# untitled.net
KiCad netlist of a schematic drawn in EAGLE
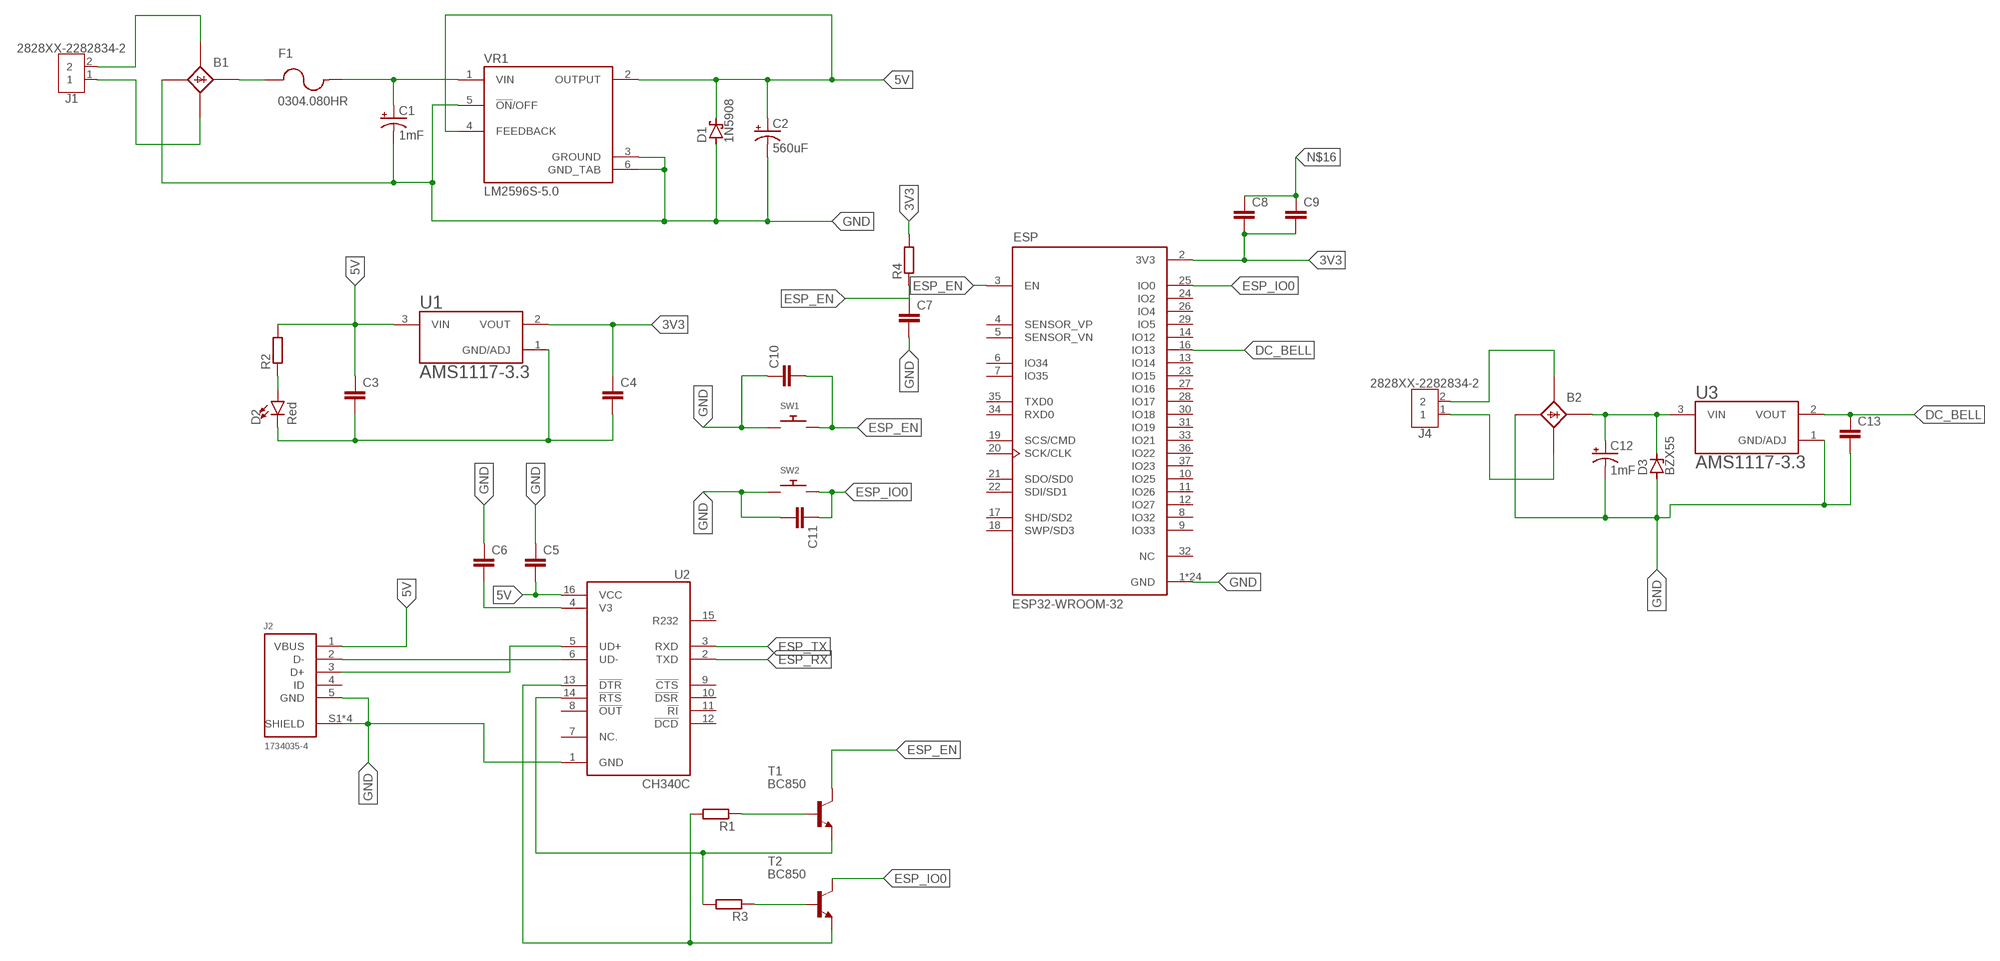
[diagram p0: schematic, sheet 1]

(export (version "E")
  (design (tool "Eeschema 10.0.6"))
  (components
    (comp (ref "B1")
      (value "B25A-")
      (footprint "eagle-import:B25A-")
      (libsource (lib "eagle-import") (part "B25A-"))
    )
    (comp (ref "B2")
      (value "B25A-")
      (footprint "eagle-import:B25A-")
      (libsource (lib "eagle-import") (part "B25A-"))
    )
    (comp (ref "C1")
      (value "1mF")
      (footprint "eagle-import:CPOL-RADIAL-5MM-10MM")
      (libsource (lib "eagle-import") (part "1000UF-RADIAL-5MM-25V-20%"))
    )
    (comp (ref "C2")
      (value "560uF")
      (footprint "eagle-import:PANASONIC_G")
      (libsource (lib "eagle-import") (part "560UF-PANASONIC_G-25V-20%"))
    )
    (comp (ref "C3")
      (value "C-EUC1206K")
      (footprint "eagle-import:C1206K")
      (libsource (lib "eagle-import") (part "C-EUC1206K"))
    )
    (comp (ref "C4")
      (value "C-EUC1206K")
      (footprint "eagle-import:C1206K")
      (libsource (lib "eagle-import") (part "C-EUC1206K"))
    )
    (comp (ref "C5")
      (value "C-EUC1206K")
      (footprint "eagle-import:C1206K")
      (libsource (lib "eagle-import") (part "C-EUC1206K"))
    )
    (comp (ref "C6")
      (value "C-EUC1206K")
      (footprint "eagle-import:C1206K")
      (libsource (lib "eagle-import") (part "C-EUC1206K"))
    )
    (comp (ref "C7")
      (value "C-EUC1206K")
      (footprint "eagle-import:C1206K")
      (libsource (lib "eagle-import") (part "C-EUC1206K"))
    )
    (comp (ref "C8")
      (value "C-EUC1206K")
      (footprint "eagle-import:C1206K")
      (libsource (lib "eagle-import") (part "C-EUC1206K"))
    )
    (comp (ref "C9")
      (value "C-EUC1206K")
      (footprint "eagle-import:C1206K")
      (libsource (lib "eagle-import") (part "C-EUC1206K"))
    )
    (comp (ref "C10")
      (value "C-EUC1206K")
      (footprint "eagle-import:C1206K")
      (libsource (lib "eagle-import") (part "C-EUC1206K"))
    )
    (comp (ref "C11")
      (value "C-EUC1206K")
      (footprint "eagle-import:C1206K")
      (libsource (lib "eagle-import") (part "C-EUC1206K"))
    )
    (comp (ref "C12")
      (value "1mF")
      (footprint "eagle-import:CPOL-RADIAL-5MM-10MM")
      (libsource (lib "eagle-import") (part "1000UF-RADIAL-5MM-25V-20%"))
    )
    (comp (ref "C13")
      (value "C-EUC1206K")
      (footprint "eagle-import:C1206K")
      (libsource (lib "eagle-import") (part "C-EUC1206K"))
    )
    (comp (ref "D1")
      (value "1N5908")
      (footprint "eagle-import:C4111-15")
      (libsource (lib "eagle-import") (part "1N5908"))
    )
    (comp (ref "D2")
      (value "Red")
      (footprint "eagle-import:LED-0603")
      (libsource (lib "eagle-import") (part "LED-RED-0603-WE"))
    )
    (comp (ref "D3")
      (value "BZX55")
      (footprint "eagle-import:DO35Z10")
      (libsource (lib "eagle-import") (part "BZX55"))
    )
    (comp (ref "ESP")
      (value "ESP32-WROOM-32")
      (footprint "eagle-import:MODULE_ESP32-WROOM-32")
      (fields (field (name "MF") "Espressif Systems"))
      (libsource (lib "eagle-import") (part "ESP32-WROOM-32"))
    )
    (comp (ref "F1")
      (value "0304.080HR")
      (footprint "eagle-import:0304.080HR")
      (fields (field (name "MANUFACTURER") "Littelfuse Inc.") (field (name "CREATED_BY") "PCBLayout.com"))
      (libsource (lib "eagle-import") (part "0304.080HR"))
    )
    (comp (ref "J1")
      (value "2828XX-2282834-2")
      (footprint "eagle-import:TERMBLK_254-2N")
      (fields (field (name "MANUFACTURER") "TE Connectivity AMP Connectors") (field (name "MPN") "282834-2 "))
      (libsource (lib "eagle-import") (part "2828XX-2282834-2"))
    )
    (comp (ref "J2")
      (value "1734035-4")
      (footprint "eagle-import:1734035-4")
      (fields
        (field (name "DIGIKEY_PARTNO") "A121554TR-ND")
        (field (name "MANUFACTURER") "TE Connectivity AMP Connectors")
        (field (name "CREATED_BY") "PCBLayout.com")
      )
      (libsource (lib "eagle-import") (part "1734035-4"))
    )
    (comp (ref "J4")
      (value "2828XX-2282834-2")
      (footprint "eagle-import:TERMBLK_254-2N")
      (fields (field (name "MANUFACTURER") "TE Connectivity AMP Connectors") (field (name "MPN") "282834-2 "))
      (libsource (lib "eagle-import") (part "2828XX-2282834-2"))
    )
    (comp (ref "R1")
      (value "R-EU_R5025W")
      (footprint "eagle-import:R5025W")
      (libsource (lib "eagle-import") (part "R-EU_R5025W"))
    )
    (comp (ref "R2")
      (value "R-EU_R5025W")
      (footprint "eagle-import:R5025W")
      (libsource (lib "eagle-import") (part "R-EU_R5025W"))
    )
    (comp (ref "R3")
      (value "R-EU_R5025W")
      (footprint "eagle-import:R5025W")
      (libsource (lib "eagle-import") (part "R-EU_R5025W"))
    )
    (comp (ref "R4")
      (value "R-EU_R5025W")
      (footprint "eagle-import:R5025W")
      (libsource (lib "eagle-import") (part "R-EU_R5025W"))
    )
    (comp (ref "SW1")
      (value "SWITCH_PUSHBUTTONSOFTTOUCHSMD_SJ")
      (footprint "eagle-import:PUSHBUTTON_SMD_SJ")
      (libsource (lib "eagle-import") (part "SWITCH_PUSHBUTTONSOFTTOUCHSMD_SJ"))
    )
    (comp (ref "SW2")
      (value "SWITCH_PUSHBUTTONSOFTTOUCHSMD_SJ")
      (footprint "eagle-import:PUSHBUTTON_SMD_SJ")
      (libsource (lib "eagle-import") (part "SWITCH_PUSHBUTTONSOFTTOUCHSMD_SJ"))
    )
    (comp (ref "T1")
      (value "BC850")
      (footprint "eagle-import:SOT23")
      (libsource (lib "eagle-import") (part "BC850"))
    )
    (comp (ref "T2")
      (value "BC850")
      (footprint "eagle-import:SOT23")
      (libsource (lib "eagle-import") (part "BC850"))
    )
    (comp (ref "U1")
      (value "AMS1117-3.3")
      (footprint "eagle-import:SOT229P700X180-4N")
      (fields (field (name "MF") "Advanced Monolithic Systems"))
      (libsource (lib "eagle-import") (part "AMS1117-3.3"))
    )
    (comp (ref "U2")
      (value "CH340C")
      (footprint "eagle-import:SOIC127P600X180-16N")
      (fields (field (name "MF") "WCH"))
      (libsource (lib "eagle-import") (part "CH340C"))
    )
    (comp (ref "U3")
      (value "AMS1117-3.3")
      (footprint "eagle-import:SOT229P700X180-4N")
      (fields (field (name "MF") "Advanced Monolithic Systems"))
      (libsource (lib "eagle-import") (part "AMS1117-3.3"))
    )
    (comp (ref "VR1")
      (value "LM2596S-5.0")
      (footprint "eagle-import:TO170P1524X483-6N")
      (fields (field (name "MF") "Texas"))
      (libsource (lib "eagle-import") (part "LM2596S-5.0"))
    )
  )
  (nets
    (net (code "1") (name "3V3") (class "Default")
      (node (ref "C4") (pin "1") (pinfunction "1_1") (pintype "passive"))
      (node (ref "C8") (pin "2") (pinfunction "2_2") (pintype "passive"))
      (node (ref "C9") (pin "2") (pinfunction "2_2") (pintype "passive"))
      (node (ref "ESP") (pin "2") (pinfunction "3V3_2") (pintype "power_in"))
      (node (ref "R4") (pin "2") (pinfunction "2_2") (pintype "passive"))
      (node (ref "U1") (pin "2") (pinfunction "VOUT_2") (pintype "output"))
    )
    (net (code "2") (name "5V") (class "Default")
      (node (ref "C2") (pin "+") (pinfunction "+_+") (pintype "passive"))
      (node (ref "C3") (pin "1") (pinfunction "1_1") (pintype "passive"))
      (node (ref "C5") (pin "2") (pinfunction "2_2") (pintype "passive"))
      (node (ref "D1") (pin "C") (pinfunction "C_C") (pintype "passive"))
      (node (ref "J2") (pin "1") (pinfunction "VBUS_1") (pintype "passive"))
      (node (ref "R2") (pin "2") (pinfunction "2_2") (pintype "passive"))
      (node (ref "U1") (pin "3") (pinfunction "VIN_3") (pintype "input"))
      (node (ref "U2") (pin "16") (pinfunction "VCC_16") (pintype "power_in"))
      (node (ref "VR1") (pin "2") (pinfunction "OUTPUT_2") (pintype "output"))
      (node (ref "VR1") (pin "4") (pinfunction "FEEDBACK_4") (pintype "input"))
    )
    (net (code "3") (name "DC_BELL") (class "Default")
      (node (ref "C13") (pin "1") (pinfunction "1_1") (pintype "passive"))
      (node (ref "ESP") (pin "16") (pinfunction "IO13_16") (pintype "bidirectional"))
      (node (ref "U3") (pin "2") (pinfunction "VOUT_2") (pintype "output"))
    )
    (net (code "4") (name "ESP_EN") (class "Default")
      (node (ref "C10") (pin "2") (pinfunction "2_2") (pintype "passive"))
      (node (ref "C7") (pin "1") (pinfunction "1_1") (pintype "passive"))
      (node (ref "ESP") (pin "3") (pinfunction "EN_3") (pintype "input"))
      (node (ref "R4") (pin "1") (pinfunction "1_1") (pintype "passive"))
      (node (ref "SW1") (pin "P$2") (pinfunction "P$2_P$2") (pintype "passive"))
      (node (ref "T1") (pin "3") (pinfunction "C_3") (pintype "passive"))
    )
    (net (code "5") (name "ESP_IO0") (class "Default")
      (node (ref "C11") (pin "1") (pinfunction "1_1") (pintype "passive"))
      (node (ref "ESP") (pin "25") (pinfunction "IO0_25") (pintype "bidirectional"))
      (node (ref "SW2") (pin "P$2") (pinfunction "P$2_P$2") (pintype "passive"))
      (node (ref "T2") (pin "3") (pinfunction "C_3") (pintype "passive"))
    )
    (net (code "6") (name "ESP_RX") (class "Default")
      (node (ref "U2") (pin "2") (pinfunction "TXD_2") (pintype "output"))
    )
    (net (code "7") (name "ESP_TX") (class "Default")
      (node (ref "U2") (pin "3") (pinfunction "RXD_3") (pintype "input"))
    )
    (net (code "8") (name "GND") (class "Default")
      (node (ref "B1") (pin "-1") (pinfunction "-_-1") (pintype "passive"))
      (node (ref "B2") (pin "-1") (pinfunction "-_-1") (pintype "passive"))
      (node (ref "C1") (pin "-") (pinfunction "-_-") (pintype "passive"))
      (node (ref "C10") (pin "1") (pinfunction "1_1") (pintype "passive"))
      (node (ref "C11") (pin "2") (pinfunction "2_2") (pintype "passive"))
      (node (ref "C12") (pin "-") (pinfunction "-_-") (pintype "passive"))
      (node (ref "C13") (pin "2") (pinfunction "2_2") (pintype "passive"))
      (node (ref "C2") (pin "-") (pinfunction "-_-") (pintype "passive"))
      (node (ref "C5") (pin "1") (pinfunction "1_1") (pintype "passive"))
      (node (ref "C6") (pin "1") (pinfunction "1_1") (pintype "passive"))
      (node (ref "C7") (pin "2") (pinfunction "2_2") (pintype "passive"))
      (node (ref "D1") (pin "A") (pinfunction "A_A") (pintype "passive"))
      (node (ref "D3") (pin "A") (pinfunction "A_A") (pintype "passive"))
      (node (ref "ESP") (pin "1") (pinfunction "GND_1") (pintype "power_in"))
      (node (ref "ESP") (pin "15") (pinfunction "GND_15") (pintype "power_in"))
      (node (ref "ESP") (pin "38") (pinfunction "GND_38") (pintype "power_in"))
      (node (ref "ESP") (pin "39_1") (pinfunction "GND_39_1") (pintype "power_in"))
      (node (ref "ESP") (pin "39_10") (pinfunction "GND_39_10") (pintype "power_in"))
      (node (ref "ESP") (pin "39_11") (pinfunction "GND_39_11") (pintype "power_in"))
      (node (ref "ESP") (pin "39_12") (pinfunction "GND_39_12") (pintype "power_in"))
      (node (ref "ESP") (pin "39_13") (pinfunction "GND_39_13") (pintype "power_in"))
      (node (ref "ESP") (pin "39_14") (pinfunction "GND_39_14") (pintype "power_in"))
      (node (ref "ESP") (pin "39_15") (pinfunction "GND_39_15") (pintype "power_in"))
      (node (ref "ESP") (pin "39_16") (pinfunction "GND_39_16") (pintype "power_in"))
      (node (ref "ESP") (pin "39_17") (pinfunction "GND_39_17") (pintype "power_in"))
      (node (ref "ESP") (pin "39_18") (pinfunction "GND_39_18") (pintype "power_in"))
      (node (ref "ESP") (pin "39_19") (pinfunction "GND_39_19") (pintype "power_in"))
      (node (ref "ESP") (pin "39_2") (pinfunction "GND_39_2") (pintype "power_in"))
      (node (ref "ESP") (pin "39_20") (pinfunction "GND_39_20") (pintype "power_in"))
      (node (ref "ESP") (pin "39_21") (pinfunction "GND_39_21") (pintype "power_in"))
      (node (ref "ESP") (pin "39_3") (pinfunction "GND_39_3") (pintype "power_in"))
      (node (ref "ESP") (pin "39_4") (pinfunction "GND_39_4") (pintype "power_in"))
      (node (ref "ESP") (pin "39_5") (pinfunction "GND_39_5") (pintype "power_in"))
      (node (ref "ESP") (pin "39_6") (pinfunction "GND_39_6") (pintype "power_in"))
      (node (ref "ESP") (pin "39_7") (pinfunction "GND_39_7") (pintype "power_in"))
      (node (ref "ESP") (pin "39_8") (pinfunction "GND_39_8") (pintype "power_in"))
      (node (ref "ESP") (pin "39_9") (pinfunction "GND_39_9") (pintype "power_in"))
      (node (ref "J2") (pin "5") (pinfunction "GND_5") (pintype "passive"))
      (node (ref "J2") (pin "S1") (pinfunction "SHIELD_S1") (pintype "power_in"))
      (node (ref "J2") (pin "S2") (pinfunction "SHIELD_S2") (pintype "power_in"))
      (node (ref "J2") (pin "S3") (pinfunction "SHIELD_S3") (pintype "power_in"))
      (node (ref "J2") (pin "S4") (pinfunction "SHIELD_S4") (pintype "power_in"))
      (node (ref "SW1") (pin "P$1") (pinfunction "P$1_P$1") (pintype "passive"))
      (node (ref "SW2") (pin "P$1") (pinfunction "P$1_P$1") (pintype "passive"))
      (node (ref "U2") (pin "1") (pinfunction "GND_1") (pintype "power_in"))
      (node (ref "U3") (pin "1") (pinfunction "GND/ADJ_1") (pintype "power_in"))
      (node (ref "VR1") (pin "3") (pinfunction "GROUND_3") (pintype "power_in"))
      (node (ref "VR1") (pin "5") (pinfunction "~{ON}/OFF_5") (pintype "input"))
      (node (ref "VR1") (pin "6") (pinfunction "GND_TAB_6") (pintype "power_in"))
    )
    (net (code "9") (name "N$16") (class "Default")
      (node (ref "C8") (pin "1") (pinfunction "1_1") (pintype "passive"))
      (node (ref "C9") (pin "1") (pinfunction "1_1") (pintype "passive"))
    )
    (net (code "10") (name "Net-(B1-+-Pad+1)") (class "Default")
      (node (ref "B1") (pin "+1") (pinfunction "+_+1") (pintype "passive"))
      (node (ref "F1") (pin "1") (pinfunction "1_1") (pintype "passive"))
    )
    (net (code "11") (name "Net-(B1-AC1-PadAC1-)") (class "Default")
      (node (ref "B1") (pin "AC1-") (pinfunction "AC1_AC1-") (pintype "passive"))
      (node (ref "J1") (pin "2") (pinfunction "2_2") (pintype "bidirectional"))
    )
    (net (code "12") (name "Net-(B1-AC2-PadAC2-)") (class "Default")
      (node (ref "B1") (pin "AC2-") (pinfunction "AC2_AC2-") (pintype "passive"))
      (node (ref "J1") (pin "1") (pinfunction "1_1") (pintype "bidirectional"))
    )
    (net (code "13") (name "Net-(B2-AC1-PadAC1-)") (class "Default")
      (node (ref "B2") (pin "AC1-") (pinfunction "AC1_AC1-") (pintype "passive"))
      (node (ref "J4") (pin "2") (pinfunction "2_2") (pintype "bidirectional"))
    )
    (net (code "14") (name "Net-(B2-AC2-PadAC2-)") (class "Default")
      (node (ref "B2") (pin "AC2-") (pinfunction "AC2_AC2-") (pintype "passive"))
      (node (ref "J4") (pin "1") (pinfunction "1_1") (pintype "bidirectional"))
    )
    (net (code "15") (name "Net-(D2-PadA)") (class "Default")
      (node (ref "D2") (pin "A") (pinfunction "A_A") (pintype "passive"))
      (node (ref "R2") (pin "1") (pinfunction "1_1") (pintype "passive"))
    )
    (net (code "16") (name "Net-(J2-D+)") (class "Default")
      (node (ref "J2") (pin "3") (pinfunction "D+_3") (pintype "passive"))
      (node (ref "U2") (pin "5") (pinfunction "UD+_5") (pintype "bidirectional"))
    )
    (net (code "17") (name "Net-(J2-D-)") (class "Default")
      (node (ref "J2") (pin "2") (pinfunction "D-_2") (pintype "passive"))
      (node (ref "U2") (pin "6") (pinfunction "UD-_6") (pintype "bidirectional"))
    )
    (net (code "18") (name "Net-(T1-B)") (class "Default")
      (node (ref "R1") (pin "1") (pinfunction "1_1") (pintype "passive"))
      (node (ref "T1") (pin "1") (pinfunction "B_1") (pintype "passive"))
    )
    (net (code "19") (name "Net-(T1-E)") (class "Default")
      (node (ref "R3") (pin "2") (pinfunction "2_2") (pintype "passive"))
      (node (ref "T1") (pin "2") (pinfunction "E_2") (pintype "passive"))
      (node (ref "U2") (pin "14") (pinfunction "~{RTS}_14") (pintype "output"))
    )
    (net (code "20") (name "Net-(T2-B)") (class "Default")
      (node (ref "R3") (pin "1") (pinfunction "1_1") (pintype "passive"))
      (node (ref "T2") (pin "1") (pinfunction "B_1") (pintype "passive"))
    )
    (net (code "21") (name "Net-(T2-E)") (class "Default")
      (node (ref "R1") (pin "2") (pinfunction "2_2") (pintype "passive"))
      (node (ref "T2") (pin "2") (pinfunction "E_2") (pintype "passive"))
      (node (ref "U2") (pin "13") (pinfunction "~{DTR}_13") (pintype "output"))
    )
    (net (code "22") (name "Net-(U1-GND{slash}ADJ)") (class "Default")
      (node (ref "C3") (pin "2") (pinfunction "2_2") (pintype "passive"))
      (node (ref "C4") (pin "2") (pinfunction "2_2") (pintype "passive"))
      (node (ref "D2") (pin "C") (pinfunction "C_C") (pintype "passive"))
      (node (ref "U1") (pin "1") (pinfunction "GND/ADJ_1") (pintype "power_in"))
    )
    (net (code "23") (name "Net-(U2-V3)") (class "Default")
      (node (ref "C6") (pin "2") (pinfunction "2_2") (pintype "passive"))
      (node (ref "U2") (pin "4") (pinfunction "V3_4") (pintype "power_in"))
    )
    (net (code "24") (name "Net-(U3-VIN)") (class "Default")
      (node (ref "B2") (pin "+1") (pinfunction "+_+1") (pintype "passive"))
      (node (ref "C12") (pin "+") (pinfunction "+_+") (pintype "passive"))
      (node (ref "D3") (pin "C") (pinfunction "C_C") (pintype "passive"))
      (node (ref "U3") (pin "3") (pinfunction "VIN_3") (pintype "input"))
    )
    (net (code "25") (name "Net-(VR1-VIN)") (class "Default")
      (node (ref "C1") (pin "+") (pinfunction "+_+") (pintype "passive"))
      (node (ref "F1") (pin "2") (pinfunction "2_2") (pintype "passive"))
      (node (ref "VR1") (pin "1") (pinfunction "VIN_1") (pintype "input"))
    )
    (net (code "26") (name "unconnected-(B1-Pad+)") (class "Default")
      (node (ref "B1") (pin "+") (pinfunction "+_+") (pintype "passive"))
    )
    (net (code "27") (name "unconnected-(B1-Pad-)") (class "Default")
      (node (ref "B1") (pin "-") (pinfunction "-_-") (pintype "passive"))
    )
    (net (code "28") (name "unconnected-(B1-PadAC1)") (class "Default")
      (node (ref "B1") (pin "AC1") (pinfunction "AC1_AC1") (pintype "passive"))
    )
    (net (code "29") (name "unconnected-(B1-PadAC2)") (class "Default")
      (node (ref "B1") (pin "AC2") (pinfunction "AC2_AC2") (pintype "passive"))
    )
    (net (code "30") (name "unconnected-(B2-Pad+)") (class "Default")
      (node (ref "B2") (pin "+") (pinfunction "+_+") (pintype "passive"))
    )
    (net (code "31") (name "unconnected-(B2-Pad-)") (class "Default")
      (node (ref "B2") (pin "-") (pinfunction "-_-") (pintype "passive"))
    )
    (net (code "32") (name "unconnected-(B2-PadAC1)") (class "Default")
      (node (ref "B2") (pin "AC1") (pinfunction "AC1_AC1") (pintype "passive"))
    )
    (net (code "33") (name "unconnected-(B2-PadAC2)") (class "Default")
      (node (ref "B2") (pin "AC2") (pinfunction "AC2_AC2") (pintype "passive"))
    )
    (net (code "34") (name "unconnected-(ESP-IO2-Pad24)") (class "Default")
      (node (ref "ESP") (pin "24") (pinfunction "IO2_24") (pintype "bidirectional"))
    )
    (net (code "35") (name "unconnected-(ESP-IO4-Pad26)") (class "Default")
      (node (ref "ESP") (pin "26") (pinfunction "IO4_26") (pintype "bidirectional"))
    )
    (net (code "36") (name "unconnected-(ESP-IO5-Pad29)") (class "Default")
      (node (ref "ESP") (pin "29") (pinfunction "IO5_29") (pintype "bidirectional"))
    )
    (net (code "37") (name "unconnected-(ESP-IO12-Pad14)") (class "Default")
      (node (ref "ESP") (pin "14") (pinfunction "IO12_14") (pintype "bidirectional"))
    )
    (net (code "38") (name "unconnected-(ESP-IO14-Pad13)") (class "Default")
      (node (ref "ESP") (pin "13") (pinfunction "IO14_13") (pintype "bidirectional"))
    )
    (net (code "39") (name "unconnected-(ESP-IO15-Pad23)") (class "Default")
      (node (ref "ESP") (pin "23") (pinfunction "IO15_23") (pintype "bidirectional"))
    )
    (net (code "40") (name "unconnected-(ESP-IO16-Pad27)") (class "Default")
      (node (ref "ESP") (pin "27") (pinfunction "IO16_27") (pintype "bidirectional"))
    )
    (net (code "41") (name "unconnected-(ESP-IO17-Pad28)") (class "Default")
      (node (ref "ESP") (pin "28") (pinfunction "IO17_28") (pintype "bidirectional"))
    )
    (net (code "42") (name "unconnected-(ESP-IO18-Pad30)") (class "Default")
      (node (ref "ESP") (pin "30") (pinfunction "IO18_30") (pintype "bidirectional"))
    )
    (net (code "43") (name "unconnected-(ESP-IO19-Pad31)") (class "Default")
      (node (ref "ESP") (pin "31") (pinfunction "IO19_31") (pintype "bidirectional"))
    )
    (net (code "44") (name "unconnected-(ESP-IO21-Pad33)") (class "Default")
      (node (ref "ESP") (pin "33") (pinfunction "IO21_33") (pintype "bidirectional"))
    )
    (net (code "45") (name "unconnected-(ESP-IO22-Pad36)") (class "Default")
      (node (ref "ESP") (pin "36") (pinfunction "IO22_36") (pintype "bidirectional"))
    )
    (net (code "46") (name "unconnected-(ESP-IO23-Pad37)") (class "Default")
      (node (ref "ESP") (pin "37") (pinfunction "IO23_37") (pintype "bidirectional"))
    )
    (net (code "47") (name "unconnected-(ESP-IO25-Pad10)") (class "Default")
      (node (ref "ESP") (pin "10") (pinfunction "IO25_10") (pintype "bidirectional"))
    )
    (net (code "48") (name "unconnected-(ESP-IO26-Pad11)") (class "Default")
      (node (ref "ESP") (pin "11") (pinfunction "IO26_11") (pintype "bidirectional"))
    )
    (net (code "49") (name "unconnected-(ESP-IO27-Pad12)") (class "Default")
      (node (ref "ESP") (pin "12") (pinfunction "IO27_12") (pintype "bidirectional"))
    )
    (net (code "50") (name "unconnected-(ESP-IO32-Pad8)") (class "Default")
      (node (ref "ESP") (pin "8") (pinfunction "IO32_8") (pintype "bidirectional"))
    )
    (net (code "51") (name "unconnected-(ESP-IO33-Pad9)") (class "Default")
      (node (ref "ESP") (pin "9") (pinfunction "IO33_9") (pintype "bidirectional"))
    )
    (net (code "52") (name "unconnected-(ESP-IO34-Pad6)") (class "Default")
      (node (ref "ESP") (pin "6") (pinfunction "IO34_6") (pintype "input"))
    )
    (net (code "53") (name "unconnected-(ESP-IO35-Pad7)") (class "Default")
      (node (ref "ESP") (pin "7") (pinfunction "IO35_7") (pintype "input"))
    )
    (net (code "54") (name "unconnected-(ESP-NC-Pad32)") (class "Default")
      (node (ref "ESP") (pin "32") (pinfunction "NC_32") (pintype "no_connect"))
    )
    (net (code "55") (name "unconnected-(ESP-RXD0-Pad34)") (class "Default")
      (node (ref "ESP") (pin "34") (pinfunction "RXD0_34") (pintype "bidirectional"))
    )
    (net (code "56") (name "unconnected-(ESP-SCK{slash}CLK-Pad20)") (class "Default")
      (node (ref "ESP") (pin "20") (pinfunction "SCK/CLK_20") (pintype "bidirectional"))
    )
    (net (code "57") (name "unconnected-(ESP-SCS{slash}CMD-Pad19)") (class "Default")
      (node (ref "ESP") (pin "19") (pinfunction "SCS/CMD_19") (pintype "bidirectional"))
    )
    (net (code "58") (name "unconnected-(ESP-SDI{slash}SD1-Pad22)") (class "Default")
      (node (ref "ESP") (pin "22") (pinfunction "SDI/SD1_22") (pintype "bidirectional"))
    )
    (net (code "59") (name "unconnected-(ESP-SDO{slash}SD0-Pad21)") (class "Default")
      (node (ref "ESP") (pin "21") (pinfunction "SDO/SD0_21") (pintype "bidirectional"))
    )
    (net (code "60") (name "unconnected-(ESP-SENSOR_VN-Pad5)") (class "Default")
      (node (ref "ESP") (pin "5") (pinfunction "SENSOR_VN_5") (pintype "input"))
    )
    (net (code "61") (name "unconnected-(ESP-SENSOR_VP-Pad4)") (class "Default")
      (node (ref "ESP") (pin "4") (pinfunction "SENSOR_VP_4") (pintype "input"))
    )
    (net (code "62") (name "unconnected-(ESP-SHD{slash}SD2-Pad17)") (class "Default")
      (node (ref "ESP") (pin "17") (pinfunction "SHD/SD2_17") (pintype "bidirectional"))
    )
    (net (code "63") (name "unconnected-(ESP-SWP{slash}SD3-Pad18)") (class "Default")
      (node (ref "ESP") (pin "18") (pinfunction "SWP/SD3_18") (pintype "bidirectional"))
    )
    (net (code "64") (name "unconnected-(ESP-TXD0-Pad35)") (class "Default")
      (node (ref "ESP") (pin "35") (pinfunction "TXD0_35") (pintype "bidirectional"))
    )
    (net (code "65") (name "unconnected-(J2-ID-Pad4)") (class "Default")
      (node (ref "J2") (pin "4") (pinfunction "ID_4") (pintype "passive"))
    )
    (net (code "66") (name "unconnected-(U2-NC.-Pad7)") (class "Default")
      (node (ref "U2") (pin "7") (pinfunction "NC._7") (pintype "no_connect"))
    )
    (net (code "67") (name "unconnected-(U2-R232-Pad15)") (class "Default")
      (node (ref "U2") (pin "15") (pinfunction "R232_15") (pintype "input"))
    )
    (net (code "68") (name "unconnected-(U2-~{CTS}-Pad9)") (class "Default")
      (node (ref "U2") (pin "9") (pinfunction "~{CTS}_9") (pintype "input"))
    )
    (net (code "69") (name "unconnected-(U2-~{DCD}-Pad12)") (class "Default")
      (node (ref "U2") (pin "12") (pinfunction "~{DCD}_12") (pintype "input"))
    )
    (net (code "70") (name "unconnected-(U2-~{DSR}-Pad10)") (class "Default")
      (node (ref "U2") (pin "10") (pinfunction "~{DSR}_10") (pintype "input"))
    )
    (net (code "71") (name "unconnected-(U2-~{OUT}-Pad8)") (class "Default")
      (node (ref "U2") (pin "8") (pinfunction "~{OUT}_8") (pintype "output"))
    )
    (net (code "72") (name "unconnected-(U2-~{RI}-Pad11)") (class "Default")
      (node (ref "U2") (pin "11") (pinfunction "~{RI}_11") (pintype "input"))
    )
  )
)
